# SCH-Connector.net
KiCad netlist of a schematic drawn in Altium Designer
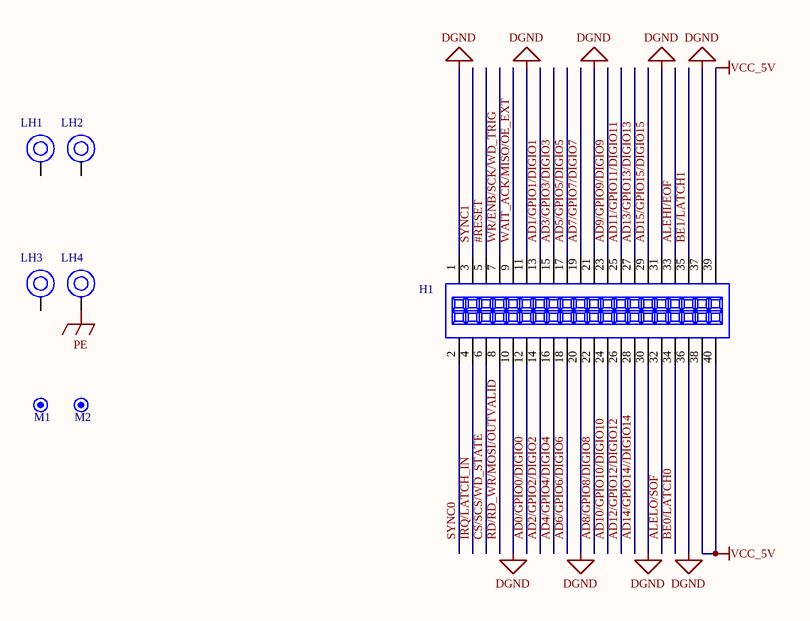
[diagram p0: SCH-Connector.SchDoc]

(export (version "E")
  (design (tool "Eeschema 10.0.6"))
  (components
    (comp (ref "H1")
      (value "直插双排母2.4/4.3")
      (footprint "2.00 mm 直插双排母2.4/4.3 2X20P")
      (description "2.00 mm 直插双排母 2.4/4.3 2X20P,2A")
      (fields
        (field (name "1ST PARTNUMBER") "703-2S-3C-2*20PS-4.3/2.4")
        (field (name "2ND PARTNUMBER") "国产可替代")
      )
      (libsource (lib "15-连接器") (part "HDR2.00mm/2x20/F"))
    )
    (comp (ref "LH1")
      (value "DPDT/24V/250VAC/30A")
      (footprint "LOCAL-HOLE-M3/5")
      (description "定位孔")
      (libsource (lib "1C-机电设备") (part "LOCAL-HOLE"))
    )
    (comp (ref "LH2")
      (value "DPDT/24V/250VAC/30A")
      (footprint "LOCAL-HOLE-M3/5")
      (description "定位孔")
      (libsource (lib "1C-机电设备") (part "LOCAL-HOLE"))
    )
    (comp (ref "LH3")
      (value "DPDT/24V/250VAC/30A")
      (footprint "LOCAL-HOLE-M3/5")
      (description "定位孔")
      (libsource (lib "1C-机电设备") (part "LOCAL-HOLE"))
    )
    (comp (ref "LH4")
      (value "DPDT/24V/250VAC/30A")
      (footprint "LOCAL-HOLE-M3/5")
      (description "定位孔")
      (libsource (lib "1C-机电设备") (part "LOCAL-HOLE"))
    )
    (comp (ref "M1")
      (value "MARK POINT")
      (footprint "MARK-POINT-1mm/2mm")
      (description "Mark点")
      (libsource (lib "1C-机电设备") (part "MARK POINT"))
    )
    (comp (ref "M2")
      (value "MARK POINT")
      (footprint "MARK-POINT-1mm/2mm")
      (description "Mark点")
      (libsource (lib "1C-机电设备") (part "MARK POINT"))
    )
  )
  (nets
    (net (code "1") (name "/#RESET") (class "Default")
      (node (ref "H1") (pin "5") (pinfunction "5_5") (pintype "passive"))
    )
    (net (code "2") (name "/AD0{slash}GPIO0{slash}DIGIO0") (class "Default")
      (node (ref "H1") (pin "12") (pinfunction "12_12") (pintype "passive"))
    )
    (net (code "3") (name "/AD1{slash}GPIO1{slash}DIGIO1") (class "Default")
      (node (ref "H1") (pin "13") (pinfunction "13_13") (pintype "passive"))
    )
    (net (code "4") (name "/AD2{slash}GPIO2{slash}DIGIO2") (class "Default")
      (node (ref "H1") (pin "14") (pinfunction "14_14") (pintype "passive"))
    )
    (net (code "5") (name "/AD3{slash}GPIO3{slash}DIGIO3") (class "Default")
      (node (ref "H1") (pin "15") (pinfunction "15_15") (pintype "passive"))
    )
    (net (code "6") (name "/AD4{slash}GPIO4{slash}DIGIO4") (class "Default")
      (node (ref "H1") (pin "16") (pinfunction "16_16") (pintype "passive"))
    )
    (net (code "7") (name "/AD5{slash}GPIO5{slash}DIGIO5") (class "Default")
      (node (ref "H1") (pin "17") (pinfunction "17_17") (pintype "passive"))
    )
    (net (code "8") (name "/AD6{slash}GPIO6{slash}DIGIO6") (class "Default")
      (node (ref "H1") (pin "18") (pinfunction "18_18") (pintype "passive"))
    )
    (net (code "9") (name "/AD7{slash}GPIO7{slash}DIGIO7") (class "Default")
      (node (ref "H1") (pin "19") (pinfunction "19_19") (pintype "passive"))
    )
    (net (code "10") (name "/AD8{slash}GPIO8{slash}DIGIO8") (class "Default")
      (node (ref "H1") (pin "22") (pinfunction "22_22") (pintype "passive"))
    )
    (net (code "11") (name "/AD9{slash}GPIO9{slash}DIGIO9") (class "Default")
      (node (ref "H1") (pin "23") (pinfunction "23_23") (pintype "passive"))
    )
    (net (code "12") (name "/AD10{slash}GPIO10{slash}DIGIO10") (class "Default")
      (node (ref "H1") (pin "24") (pinfunction "24_24") (pintype "passive"))
    )
    (net (code "13") (name "/AD11{slash}GPIO11{slash}DIGIO11") (class "Default")
      (node (ref "H1") (pin "25") (pinfunction "25_25") (pintype "passive"))
    )
    (net (code "14") (name "/AD12{slash}GPIO12{slash}DIGIO12") (class "Default")
      (node (ref "H1") (pin "26") (pinfunction "26_26") (pintype "passive"))
    )
    (net (code "15") (name "/AD13{slash}GPIO13{slash}DIGIO13") (class "Default")
      (node (ref "H1") (pin "27") (pinfunction "27_27") (pintype "passive"))
    )
    (net (code "16") (name "/AD14{slash}GPIO14{slash}{slash}DIGIO14") (class "Default")
      (node (ref "H1") (pin "28") (pinfunction "28_28") (pintype "passive"))
    )
    (net (code "17") (name "/AD15{slash}GPIO15{slash}DIGIO15") (class "Default")
      (node (ref "H1") (pin "29") (pinfunction "29_29") (pintype "passive"))
    )
    (net (code "18") (name "/ALEHI{slash}EOF") (class "Default")
      (node (ref "H1") (pin "33") (pinfunction "33_33") (pintype "passive"))
    )
    (net (code "19") (name "/ALELO{slash}SOF") (class "Default")
      (node (ref "H1") (pin "32") (pinfunction "32_32") (pintype "passive"))
    )
    (net (code "20") (name "/BE0{slash}LATCH0") (class "Default")
      (node (ref "H1") (pin "34") (pinfunction "34_34") (pintype "passive"))
    )
    (net (code "21") (name "/BE1{slash}LATCH1") (class "Default")
      (node (ref "H1") (pin "35") (pinfunction "35_35") (pintype "passive"))
    )
    (net (code "22") (name "/CS{slash}SCS{slash}WD_STATE") (class "Default")
      (node (ref "H1") (pin "6") (pinfunction "6_6") (pintype "passive"))
    )
    (net (code "23") (name "/IRQ{slash}LATCH_IN") (class "Default")
      (node (ref "H1") (pin "4") (pinfunction "4_4") (pintype "passive"))
    )
    (net (code "24") (name "/RD{slash}RD_WR{slash}MOSI{slash}OUTVALID") (class "Default")
      (node (ref "H1") (pin "8") (pinfunction "8_8") (pintype "passive"))
    )
    (net (code "25") (name "/SYNC0") (class "Default")
      (node (ref "H1") (pin "2") (pinfunction "2_2") (pintype "passive"))
    )
    (net (code "26") (name "/SYNC1") (class "Default")
      (node (ref "H1") (pin "3") (pinfunction "3_3") (pintype "passive"))
    )
    (net (code "27") (name "/WAIT_ACK{slash}MISO{slash}OE_EXT") (class "Default")
      (node (ref "H1") (pin "9") (pinfunction "9_9") (pintype "passive"))
    )
    (net (code "28") (name "/WR{slash}ENB{slash}SCK{slash}WD_TRIG") (class "Default")
      (node (ref "H1") (pin "7") (pinfunction "7_7") (pintype "passive"))
    )
    (net (code "29") (name "DGND") (class "Default")
      (node (ref "H1") (pin "1") (pinfunction "1_1") (pintype "passive"))
      (node (ref "H1") (pin "10") (pinfunction "10_10") (pintype "passive"))
      (node (ref "H1") (pin "11") (pinfunction "11_11") (pintype "passive"))
      (node (ref "H1") (pin "20") (pinfunction "20_20") (pintype "passive"))
      (node (ref "H1") (pin "21") (pinfunction "21_21") (pintype "passive"))
      (node (ref "H1") (pin "30") (pinfunction "30_30") (pintype "passive"))
      (node (ref "H1") (pin "31") (pinfunction "31_31") (pintype "passive"))
      (node (ref "H1") (pin "36") (pinfunction "36_36") (pintype "passive"))
      (node (ref "H1") (pin "37") (pinfunction "37_37") (pintype "passive"))
    )
    (net (code "30") (name "PE") (class "Default")
      (node (ref "LH4") (pin "0") (pinfunction "0_0") (pintype "passive"))
    )
    (net (code "31") (name "VCC_5V") (class "Default")
      (node (ref "H1") (pin "38") (pinfunction "38_38") (pintype "passive"))
      (node (ref "H1") (pin "39") (pinfunction "39_39") (pintype "passive"))
      (node (ref "H1") (pin "40") (pinfunction "40_40") (pintype "passive"))
    )
    (net (code "32") (name "unconnected-(LH1-Pad0)") (class "Default")
      (node (ref "LH1") (pin "0") (pinfunction "0_0") (pintype "passive"))
    )
    (net (code "33") (name "unconnected-(LH2-Pad0)") (class "Default")
      (node (ref "LH2") (pin "0") (pinfunction "0_0") (pintype "passive"))
    )
    (net (code "34") (name "unconnected-(LH3-Pad0)") (class "Default")
      (node (ref "LH3") (pin "0") (pinfunction "0_0") (pintype "passive"))
    )
  )
)
